# MiniBoard.net
KiCad netlist of a schematic drawn in EAGLE
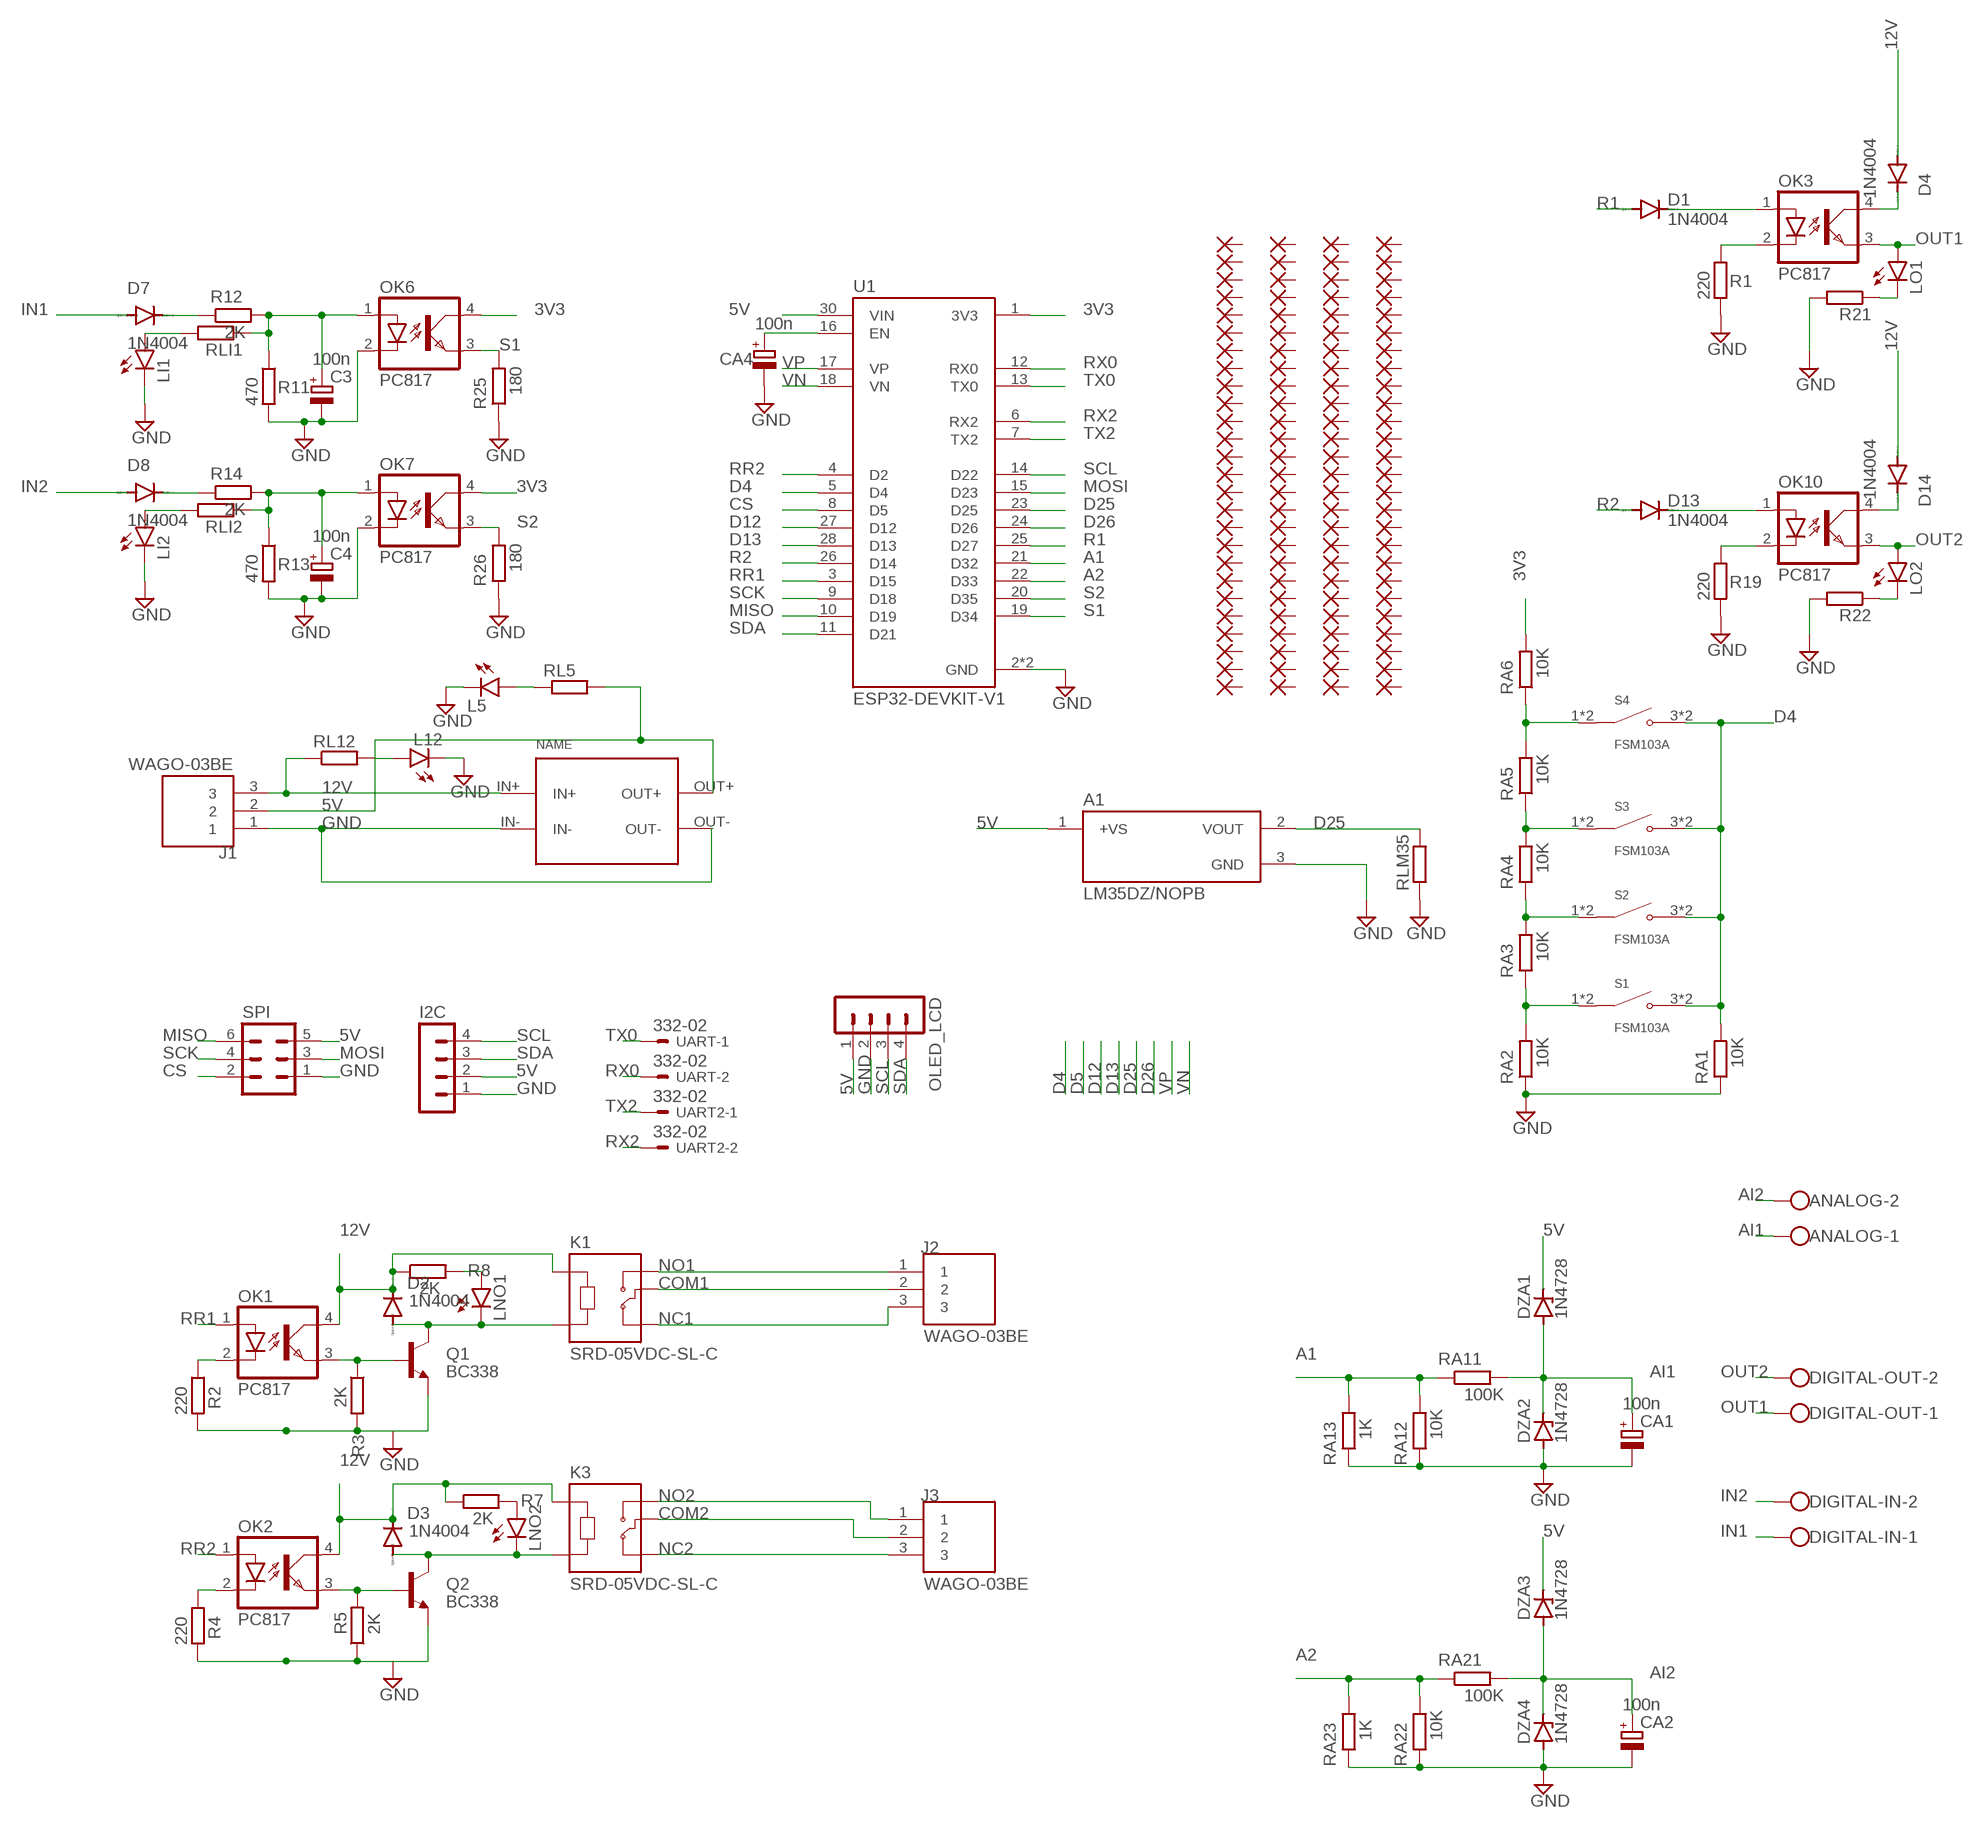
[diagram p0: schematic, sheet 1]

(export (version "E")
  (design (tool "Eeschema 10.0.6"))
  (components
    (comp (ref "A1")
      (value "LM35DZ/NOPB")
      (footprint "eagle-import:TO92127P521H735-3")
      (fields (field (name "DIGIKEY_PART_NUMBER") "LM35DZ/NOPB-ND") (field (name "MF") "Texas"))
      (libsource (lib "eagle-import") (part "LM35DZ/NOPB"))
    )
    (comp (ref "ANALOG")
      (value "W237-102")
      (footprint "eagle-import:W237-102")
      (fields (field (name "MPN") "237-102"))
      (libsource (lib "eagle-import") (part "W237-102"))
    )
    (comp (ref "C3")
      (value "100n")
      (footprint "eagle-import:E5-6")
      (libsource (lib "eagle-import") (part "CPOL-EUE5-6"))
    )
    (comp (ref "C4")
      (value "100n")
      (footprint "eagle-import:E5-6")
      (libsource (lib "eagle-import") (part "CPOL-EUE5-6"))
    )
    (comp (ref "CA1")
      (value "100n")
      (footprint "eagle-import:E5-6")
      (libsource (lib "eagle-import") (part "CPOL-EUE5-6"))
    )
    (comp (ref "CA2")
      (value "100n")
      (footprint "eagle-import:E5-6")
      (libsource (lib "eagle-import") (part "CPOL-EUE5-6"))
    )
    (comp (ref "CA4")
      (value "100n")
      (footprint "eagle-import:E5-6")
      (libsource (lib "eagle-import") (part "CPOL-EUE5-6"))
    )
    (comp (ref "D1")
      (value "1N4004")
      (footprint "eagle-import:DO41-10")
      (libsource (lib "eagle-import") (part "1N4004"))
    )
    (comp (ref "D2")
      (value "1N4004")
      (footprint "eagle-import:DO41-10")
      (libsource (lib "eagle-import") (part "1N4004"))
    )
    (comp (ref "D3")
      (value "1N4004")
      (footprint "eagle-import:DO41-10")
      (libsource (lib "eagle-import") (part "1N4004"))
    )
    (comp (ref "D4")
      (value "1N4004")
      (footprint "eagle-import:DO41-10")
      (libsource (lib "eagle-import") (part "1N4004"))
    )
    (comp (ref "D7")
      (value "1N4004")
      (footprint "eagle-import:DO41-10")
      (libsource (lib "eagle-import") (part "1N4004"))
    )
    (comp (ref "D8")
      (value "1N4004")
      (footprint "eagle-import:DO41-10")
      (libsource (lib "eagle-import") (part "1N4004"))
    )
    (comp (ref "D13")
      (value "1N4004")
      (footprint "eagle-import:DO41-10")
      (libsource (lib "eagle-import") (part "1N4004"))
    )
    (comp (ref "D14")
      (value "1N4004")
      (footprint "eagle-import:DO41-10")
      (libsource (lib "eagle-import") (part "1N4004"))
    )
    (comp (ref "DIGITAL-IN")
      (value "W237-102")
      (footprint "eagle-import:W237-102")
      (fields (field (name "MPN") "237-102"))
      (libsource (lib "eagle-import") (part "W237-102"))
    )
    (comp (ref "DIGITAL-OUT")
      (value "W237-102")
      (footprint "eagle-import:W237-102")
      (fields (field (name "MPN") "237-102"))
      (libsource (lib "eagle-import") (part "W237-102"))
    )
    (comp (ref "DZA1")
      (value "1N4728")
      (footprint "eagle-import:DO41Z10")
      (libsource (lib "eagle-import") (part "1N4728"))
    )
    (comp (ref "DZA2")
      (value "1N4728")
      (footprint "eagle-import:DO41Z10")
      (libsource (lib "eagle-import") (part "1N4728"))
    )
    (comp (ref "DZA3")
      (value "1N4728")
      (footprint "eagle-import:DO41Z10")
      (libsource (lib "eagle-import") (part "1N4728"))
    )
    (comp (ref "DZA4")
      (value "1N4728")
      (footprint "eagle-import:DO41Z10")
      (libsource (lib "eagle-import") (part "1N4728"))
    )
    (comp (ref "I2C")
      (value "MA04-1")
      (footprint "eagle-import:MA04-1")
      (libsource (lib "eagle-import") (part "MA04-1"))
    )
    (comp (ref "J1")
      (value "WAGO-03BE")
      (footprint "eagle-import:CUI_TB006-508-03BE")
      (fields (field (name "MF") "Same Sky") (field (name "MP") "TB006-508-03BE"))
      (libsource (lib "eagle-import") (part "WAGO-03BE"))
    )
    (comp (ref "J2")
      (value "WAGO-03BE")
      (footprint "eagle-import:CUI_TB006-508-03BE")
      (fields (field (name "MF") "Same Sky") (field (name "MP") "TB006-508-03BE"))
      (libsource (lib "eagle-import") (part "WAGO-03BE"))
    )
    (comp (ref "J3")
      (value "WAGO-03BE")
      (footprint "eagle-import:CUI_TB006-508-03BE")
      (fields (field (name "MF") "Same Sky") (field (name "MP") "TB006-508-03BE"))
      (libsource (lib "eagle-import") (part "WAGO-03BE"))
    )
    (comp (ref "K1")
      (value "SRD-05VDC-SL-C")
      (footprint "eagle-import:RELAY_SRD-05VDC-SL-C")
      (fields (field (name "MF") "Songle Relay"))
      (libsource (lib "eagle-import") (part "SRD-05VDC-SL-C"))
    )
    (comp (ref "K3")
      (value "SRD-05VDC-SL-C")
      (footprint "eagle-import:RELAY_SRD-05VDC-SL-C")
      (fields (field (name "MF") "Songle Relay"))
      (libsource (lib "eagle-import") (part "SRD-05VDC-SL-C"))
    )
    (comp (ref "L5")
      (value "LED3MM")
      (footprint "eagle-import:LED3MM")
      (libsource (lib "eagle-import") (part "LED3MM"))
    )
    (comp (ref "L12")
      (value "LED3MM")
      (footprint "eagle-import:LED3MM")
      (libsource (lib "eagle-import") (part "LED3MM"))
    )
    (comp (ref "LI1")
      (value "LED3MM")
      (footprint "eagle-import:LED3MM")
      (libsource (lib "eagle-import") (part "LED3MM"))
    )
    (comp (ref "LI2")
      (value "LED3MM")
      (footprint "eagle-import:LED3MM")
      (libsource (lib "eagle-import") (part "LED3MM"))
    )
    (comp (ref "LNO1")
      (value "LED3MM")
      (footprint "eagle-import:LED3MM")
      (libsource (lib "eagle-import") (part "LED3MM"))
    )
    (comp (ref "LNO2")
      (value "LED3MM")
      (footprint "eagle-import:LED3MM")
      (libsource (lib "eagle-import") (part "LED3MM"))
    )
    (comp (ref "LO1")
      (value "LED3MM")
      (footprint "eagle-import:LED3MM")
      (libsource (lib "eagle-import") (part "LED3MM"))
    )
    (comp (ref "LO2")
      (value "LED3MM")
      (footprint "eagle-import:LED3MM")
      (libsource (lib "eagle-import") (part "LED3MM"))
    )
    (comp (ref "OK1")
      (value "PC817")
      (footprint "eagle-import:DIL04")
      (fields (field (name "MPN") "PC817X4J000F"))
      (libsource (lib "eagle-import") (part "PC817"))
    )
    (comp (ref "OK2")
      (value "PC817")
      (footprint "eagle-import:DIL04")
      (fields (field (name "MPN") "PC817X4J000F"))
      (libsource (lib "eagle-import") (part "PC817"))
    )
    (comp (ref "OK3")
      (value "PC817")
      (footprint "eagle-import:DIL04")
      (fields (field (name "MPN") "PC817X4J000F"))
      (libsource (lib "eagle-import") (part "PC817"))
    )
    (comp (ref "OK6")
      (value "PC817")
      (footprint "eagle-import:DIL04")
      (fields (field (name "MPN") "PC817X4J000F"))
      (libsource (lib "eagle-import") (part "PC817"))
    )
    (comp (ref "OK7")
      (value "PC817")
      (footprint "eagle-import:DIL04")
      (fields (field (name "MPN") "PC817X4J000F"))
      (libsource (lib "eagle-import") (part "PC817"))
    )
    (comp (ref "OK10")
      (value "PC817")
      (footprint "eagle-import:DIL04")
      (fields (field (name "MPN") "PC817X4J000F"))
      (libsource (lib "eagle-import") (part "PC817"))
    )
    (comp (ref "OLED_LCD")
      (value "MA04-1")
      (footprint "eagle-import:MA04-1")
      (libsource (lib "eagle-import") (part "MA04-1"))
    )
    (comp (ref "PAD1")
      (value "WIREPAD1,6/0,9")
      (footprint "eagle-import:1,6_0,9")
      (libsource (lib "eagle-import") (part "WIREPAD1,6/0,9"))
    )
    (comp (ref "PAD2")
      (value "WIREPAD1,6/0,9")
      (footprint "eagle-import:1,6_0,9")
      (libsource (lib "eagle-import") (part "WIREPAD1,6/0,9"))
    )
    (comp (ref "PAD3")
      (value "WIREPAD1,6/0,9")
      (footprint "eagle-import:1,6_0,9")
      (libsource (lib "eagle-import") (part "WIREPAD1,6/0,9"))
    )
    (comp (ref "PAD4")
      (value "WIREPAD1,6/0,9")
      (footprint "eagle-import:1,6_0,9")
      (libsource (lib "eagle-import") (part "WIREPAD1,6/0,9"))
    )
    (comp (ref "PAD5")
      (value "WIREPAD1,6/0,9")
      (footprint "eagle-import:1,6_0,9")
      (libsource (lib "eagle-import") (part "WIREPAD1,6/0,9"))
    )
    (comp (ref "PAD6")
      (value "WIREPAD1,6/0,9")
      (footprint "eagle-import:1,6_0,9")
      (libsource (lib "eagle-import") (part "WIREPAD1,6/0,9"))
    )
    (comp (ref "PAD7")
      (value "WIREPAD1,6/0,9")
      (footprint "eagle-import:1,6_0,9")
      (libsource (lib "eagle-import") (part "WIREPAD1,6/0,9"))
    )
    (comp (ref "PAD8")
      (value "WIREPAD1,6/0,9")
      (footprint "eagle-import:1,6_0,9")
      (libsource (lib "eagle-import") (part "WIREPAD1,6/0,9"))
    )
    (comp (ref "PAD9")
      (value "WIREPAD1,6/0,9")
      (footprint "eagle-import:1,6_0,9")
      (libsource (lib "eagle-import") (part "WIREPAD1,6/0,9"))
    )
    (comp (ref "PAD10")
      (value "WIREPAD1,6/0,9")
      (footprint "eagle-import:1,6_0,9")
      (libsource (lib "eagle-import") (part "WIREPAD1,6/0,9"))
    )
    (comp (ref "PAD11")
      (value "WIREPAD1,6/0,9")
      (footprint "eagle-import:1,6_0,9")
      (libsource (lib "eagle-import") (part "WIREPAD1,6/0,9"))
    )
    (comp (ref "PAD12")
      (value "WIREPAD1,6/0,9")
      (footprint "eagle-import:1,6_0,9")
      (libsource (lib "eagle-import") (part "WIREPAD1,6/0,9"))
    )
    (comp (ref "PAD13")
      (value "WIREPAD1,6/0,9")
      (footprint "eagle-import:1,6_0,9")
      (libsource (lib "eagle-import") (part "WIREPAD1,6/0,9"))
    )
    (comp (ref "PAD14")
      (value "WIREPAD1,6/0,9")
      (footprint "eagle-import:1,6_0,9")
      (libsource (lib "eagle-import") (part "WIREPAD1,6/0,9"))
    )
    (comp (ref "PAD15")
      (value "WIREPAD1,6/0,9")
      (footprint "eagle-import:1,6_0,9")
      (libsource (lib "eagle-import") (part "WIREPAD1,6/0,9"))
    )
    (comp (ref "PAD16")
      (value "WIREPAD1,6/0,9")
      (footprint "eagle-import:1,6_0,9")
      (libsource (lib "eagle-import") (part "WIREPAD1,6/0,9"))
    )
    (comp (ref "PAD17")
      (value "WIREPAD1,6/0,9")
      (footprint "eagle-import:1,6_0,9")
      (libsource (lib "eagle-import") (part "WIREPAD1,6/0,9"))
    )
    (comp (ref "PAD18")
      (value "WIREPAD1,6/0,9")
      (footprint "eagle-import:1,6_0,9")
      (libsource (lib "eagle-import") (part "WIREPAD1,6/0,9"))
    )
    (comp (ref "PAD19")
      (value "WIREPAD1,6/0,9")
      (footprint "eagle-import:1,6_0,9")
      (libsource (lib "eagle-import") (part "WIREPAD1,6/0,9"))
    )
    (comp (ref "PAD20")
      (value "WIREPAD1,6/0,9")
      (footprint "eagle-import:1,6_0,9")
      (libsource (lib "eagle-import") (part "WIREPAD1,6/0,9"))
    )
    (comp (ref "PAD21")
      (value "WIREPAD1,6/0,9")
      (footprint "eagle-import:1,6_0,9")
      (libsource (lib "eagle-import") (part "WIREPAD1,6/0,9"))
    )
    (comp (ref "PAD22")
      (value "WIREPAD1,6/0,9")
      (footprint "eagle-import:1,6_0,9")
      (libsource (lib "eagle-import") (part "WIREPAD1,6/0,9"))
    )
    (comp (ref "PAD23")
      (value "WIREPAD1,6/0,9")
      (footprint "eagle-import:1,6_0,9")
      (libsource (lib "eagle-import") (part "WIREPAD1,6/0,9"))
    )
    (comp (ref "PAD24")
      (value "WIREPAD1,6/0,9")
      (footprint "eagle-import:1,6_0,9")
      (libsource (lib "eagle-import") (part "WIREPAD1,6/0,9"))
    )
    (comp (ref "PAD25")
      (value "WIREPAD1,6/0,9")
      (footprint "eagle-import:1,6_0,9")
      (libsource (lib "eagle-import") (part "WIREPAD1,6/0,9"))
    )
    (comp (ref "PAD26")
      (value "WIREPAD1,6/0,9")
      (footprint "eagle-import:1,6_0,9")
      (libsource (lib "eagle-import") (part "WIREPAD1,6/0,9"))
    )
    (comp (ref "PAD27")
      (value "WIREPAD1,6/0,9")
      (footprint "eagle-import:1,6_0,9")
      (libsource (lib "eagle-import") (part "WIREPAD1,6/0,9"))
    )
    (comp (ref "PAD28")
      (value "WIREPAD1,6/0,9")
      (footprint "eagle-import:1,6_0,9")
      (libsource (lib "eagle-import") (part "WIREPAD1,6/0,9"))
    )
    (comp (ref "PAD29")
      (value "WIREPAD1,6/0,9")
      (footprint "eagle-import:1,6_0,9")
      (libsource (lib "eagle-import") (part "WIREPAD1,6/0,9"))
    )
    (comp (ref "PAD30")
      (value "WIREPAD1,6/0,9")
      (footprint "eagle-import:1,6_0,9")
      (libsource (lib "eagle-import") (part "WIREPAD1,6/0,9"))
    )
    (comp (ref "PAD31")
      (value "WIREPAD1,6/0,9")
      (footprint "eagle-import:1,6_0,9")
      (libsource (lib "eagle-import") (part "WIREPAD1,6/0,9"))
    )
    (comp (ref "PAD32")
      (value "WIREPAD1,6/0,9")
      (footprint "eagle-import:1,6_0,9")
      (libsource (lib "eagle-import") (part "WIREPAD1,6/0,9"))
    )
    (comp (ref "PAD33")
      (value "WIREPAD1,6/0,9")
      (footprint "eagle-import:1,6_0,9")
      (libsource (lib "eagle-import") (part "WIREPAD1,6/0,9"))
    )
    (comp (ref "PAD34")
      (value "WIREPAD1,6/0,9")
      (footprint "eagle-import:1,6_0,9")
      (libsource (lib "eagle-import") (part "WIREPAD1,6/0,9"))
    )
    (comp (ref "PAD35")
      (value "WIREPAD1,6/0,9")
      (footprint "eagle-import:1,6_0,9")
      (libsource (lib "eagle-import") (part "WIREPAD1,6/0,9"))
    )
    (comp (ref "PAD36")
      (value "WIREPAD1,6/0,9")
      (footprint "eagle-import:1,6_0,9")
      (libsource (lib "eagle-import") (part "WIREPAD1,6/0,9"))
    )
    (comp (ref "PAD37")
      (value "WIREPAD1,6/0,9")
      (footprint "eagle-import:1,6_0,9")
      (libsource (lib "eagle-import") (part "WIREPAD1,6/0,9"))
    )
    (comp (ref "PAD38")
      (value "WIREPAD1,6/0,9")
      (footprint "eagle-import:1,6_0,9")
      (libsource (lib "eagle-import") (part "WIREPAD1,6/0,9"))
    )
    (comp (ref "PAD39")
      (value "WIREPAD1,6/0,9")
      (footprint "eagle-import:1,6_0,9")
      (libsource (lib "eagle-import") (part "WIREPAD1,6/0,9"))
    )
    (comp (ref "PAD40")
      (value "WIREPAD1,6/0,9")
      (footprint "eagle-import:1,6_0,9")
      (libsource (lib "eagle-import") (part "WIREPAD1,6/0,9"))
    )
    (comp (ref "PAD41")
      (value "WIREPAD1,6/0,9")
      (footprint "eagle-import:1,6_0,9")
      (libsource (lib "eagle-import") (part "WIREPAD1,6/0,9"))
    )
    (comp (ref "PAD42")
      (value "WIREPAD1,6/0,9")
      (footprint "eagle-import:1,6_0,9")
      (libsource (lib "eagle-import") (part "WIREPAD1,6/0,9"))
    )
    (comp (ref "PAD43")
      (value "WIREPAD1,6/0,9")
      (footprint "eagle-import:1,6_0,9")
      (libsource (lib "eagle-import") (part "WIREPAD1,6/0,9"))
    )
    (comp (ref "PAD44")
      (value "WIREPAD1,6/0,9")
      (footprint "eagle-import:1,6_0,9")
      (libsource (lib "eagle-import") (part "WIREPAD1,6/0,9"))
    )
    (comp (ref "PAD45")
      (value "WIREPAD1,6/0,9")
      (footprint "eagle-import:1,6_0,9")
      (libsource (lib "eagle-import") (part "WIREPAD1,6/0,9"))
    )
    (comp (ref "PAD46")
      (value "WIREPAD1,6/0,9")
      (footprint "eagle-import:1,6_0,9")
      (libsource (lib "eagle-import") (part "WIREPAD1,6/0,9"))
    )
    (comp (ref "PAD47")
      (value "WIREPAD1,6/0,9")
      (footprint "eagle-import:1,6_0,9")
      (libsource (lib "eagle-import") (part "WIREPAD1,6/0,9"))
    )
    (comp (ref "PAD48")
      (value "WIREPAD1,6/0,9")
      (footprint "eagle-import:1,6_0,9")
      (libsource (lib "eagle-import") (part "WIREPAD1,6/0,9"))
    )
    (comp (ref "PAD49")
      (value "WIREPAD1,6/0,9")
      (footprint "eagle-import:1,6_0,9")
      (libsource (lib "eagle-import") (part "WIREPAD1,6/0,9"))
    )
    (comp (ref "PAD50")
      (value "WIREPAD1,6/0,9")
      (footprint "eagle-import:1,6_0,9")
      (libsource (lib "eagle-import") (part "WIREPAD1,6/0,9"))
    )
    (comp (ref "PAD51")
      (value "WIREPAD1,6/0,9")
      (footprint "eagle-import:1,6_0,9")
      (libsource (lib "eagle-import") (part "WIREPAD1,6/0,9"))
    )
    (comp (ref "PAD52")
      (value "WIREPAD1,6/0,9")
      (footprint "eagle-import:1,6_0,9")
      (libsource (lib "eagle-import") (part "WIREPAD1,6/0,9"))
    )
    (comp (ref "PAD53")
      (value "WIREPAD1,6/0,9")
      (footprint "eagle-import:1,6_0,9")
      (libsource (lib "eagle-import") (part "WIREPAD1,6/0,9"))
    )
    (comp (ref "PAD54")
      (value "WIREPAD1,6/0,9")
      (footprint "eagle-import:1,6_0,9")
      (libsource (lib "eagle-import") (part "WIREPAD1,6/0,9"))
    )
    (comp (ref "PAD55")
      (value "WIREPAD1,6/0,9")
      (footprint "eagle-import:1,6_0,9")
      (libsource (lib "eagle-import") (part "WIREPAD1,6/0,9"))
    )
    (comp (ref "PAD56")
      (value "WIREPAD1,6/0,9")
      (footprint "eagle-import:1,6_0,9")
      (libsource (lib "eagle-import") (part "WIREPAD1,6/0,9"))
    )
    (comp (ref "PAD57")
      (value "WIREPAD1,6/0,9")
      (footprint "eagle-import:1,6_0,9")
      (libsource (lib "eagle-import") (part "WIREPAD1,6/0,9"))
    )
    (comp (ref "PAD58")
      (value "WIREPAD1,6/0,9")
      (footprint "eagle-import:1,6_0,9")
      (libsource (lib "eagle-import") (part "WIREPAD1,6/0,9"))
    )
    (comp (ref "PAD59")
      (value "WIREPAD1,6/0,9")
      (footprint "eagle-import:1,6_0,9")
      (libsource (lib "eagle-import") (part "WIREPAD1,6/0,9"))
    )
    (comp (ref "PAD60")
      (value "WIREPAD1,6/0,9")
      (footprint "eagle-import:1,6_0,9")
      (libsource (lib "eagle-import") (part "WIREPAD1,6/0,9"))
    )
    (comp (ref "PAD61")
      (value "WIREPAD1,6/0,9")
      (footprint "eagle-import:1,6_0,9")
      (libsource (lib "eagle-import") (part "WIREPAD1,6/0,9"))
    )
    (comp (ref "PAD62")
      (value "WIREPAD1,6/0,9")
      (footprint "eagle-import:1,6_0,9")
      (libsource (lib "eagle-import") (part "WIREPAD1,6/0,9"))
    )
    (comp (ref "PAD63")
      (value "WIREPAD1,6/0,9")
      (footprint "eagle-import:1,6_0,9")
      (libsource (lib "eagle-import") (part "WIREPAD1,6/0,9"))
    )
    (comp (ref "PAD64")
      (value "WIREPAD1,6/0,9")
      (footprint "eagle-import:1,6_0,9")
      (libsource (lib "eagle-import") (part "WIREPAD1,6/0,9"))
    )
    (comp (ref "PAD65")
      (value "WIREPAD1,6/0,9")
      (footprint "eagle-import:1,6_0,9")
      (libsource (lib "eagle-import") (part "WIREPAD1,6/0,9"))
    )
    (comp (ref "PAD66")
      (value "WIREPAD1,6/0,9")
      (footprint "eagle-import:1,6_0,9")
      (libsource (lib "eagle-import") (part "WIREPAD1,6/0,9"))
    )
    (comp (ref "PAD67")
      (value "WIREPAD1,6/0,9")
      (footprint "eagle-import:1,6_0,9")
      (libsource (lib "eagle-import") (part "WIREPAD1,6/0,9"))
    )
    (comp (ref "PAD68")
      (value "WIREPAD1,6/0,9")
      (footprint "eagle-import:1,6_0,9")
      (libsource (lib "eagle-import") (part "WIREPAD1,6/0,9"))
    )
    (comp (ref "PAD69")
      (value "WIREPAD1,6/0,9")
      (footprint "eagle-import:1,6_0,9")
      (libsource (lib "eagle-import") (part "WIREPAD1,6/0,9"))
    )
    (comp (ref "PAD70")
      (value "WIREPAD1,6/0,9")
      (footprint "eagle-import:1,6_0,9")
      (libsource (lib "eagle-import") (part "WIREPAD1,6/0,9"))
    )
    (comp (ref "PAD71")
      (value "WIREPAD1,6/0,9")
      (footprint "eagle-import:1,6_0,9")
      (libsource (lib "eagle-import") (part "WIREPAD1,6/0,9"))
    )
    (comp (ref "PAD72")
      (value "WIREPAD1,6/0,9")
      (footprint "eagle-import:1,6_0,9")
      (libsource (lib "eagle-import") (part "WIREPAD1,6/0,9"))
    )
    (comp (ref "PAD73")
      (value "WIREPAD1,6/0,9")
      (footprint "eagle-import:1,6_0,9")
      (libsource (lib "eagle-import") (part "WIREPAD1,6/0,9"))
    )
    (comp (ref "PAD74")
      (value "WIREPAD1,6/0,9")
      (footprint "eagle-import:1,6_0,9")
      (libsource (lib "eagle-import") (part "WIREPAD1,6/0,9"))
    )
    (comp (ref "PAD75")
      (value "WIREPAD1,6/0,9")
      (footprint "eagle-import:1,6_0,9")
      (libsource (lib "eagle-import") (part "WIREPAD1,6/0,9"))
    )
    (comp (ref "PAD76")
      (value "WIREPAD1,6/0,9")
      (footprint "eagle-import:1,6_0,9")
      (libsource (lib "eagle-import") (part "WIREPAD1,6/0,9"))
    )
    (comp (ref "PAD77")
      (value "WIREPAD1,6/0,9")
      (footprint "eagle-import:1,6_0,9")
      (libsource (lib "eagle-import") (part "WIREPAD1,6/0,9"))
    )
    (comp (ref "PAD78")
      (value "WIREPAD1,6/0,9")
      (footprint "eagle-import:1,6_0,9")
      (libsource (lib "eagle-import") (part "WIREPAD1,6/0,9"))
    )
    (comp (ref "PAD79")
      (value "WIREPAD1,6/0,9")
      (footprint "eagle-import:1,6_0,9")
      (libsource (lib "eagle-import") (part "WIREPAD1,6/0,9"))
    )
    (comp (ref "PAD80")
      (value "WIREPAD1,6/0,9")
      (footprint "eagle-import:1,6_0,9")
      (libsource (lib "eagle-import") (part "WIREPAD1,6/0,9"))
    )
    (comp (ref "PAD81")
      (value "WIREPAD1,6/0,9")
      (footprint "eagle-import:1,6_0,9")
      (libsource (lib "eagle-import") (part "WIREPAD1,6/0,9"))
    )
    (comp (ref "PAD82")
      (value "WIREPAD1,6/0,9")
      (footprint "eagle-import:1,6_0,9")
      (libsource (lib "eagle-import") (part "WIREPAD1,6/0,9"))
    )
    (comp (ref "PAD83")
      (value "WIREPAD1,6/0,9")
      (footprint "eagle-import:1,6_0,9")
      (libsource (lib "eagle-import") (part "WIREPAD1,6/0,9"))
    )
    (comp (ref "PAD84")
      (value "WIREPAD1,6/0,9")
      (footprint "eagle-import:1,6_0,9")
      (libsource (lib "eagle-import") (part "WIREPAD1,6/0,9"))
    )
    (comp (ref "PAD85")
      (value "WIREPAD1,6/0,9")
      (footprint "eagle-import:1,6_0,9")
      (libsource (lib "eagle-import") (part "WIREPAD1,6/0,9"))
    )
    (comp (ref "PAD86")
      (value "WIREPAD1,6/0,9")
      (footprint "eagle-import:1,6_0,9")
      (libsource (lib "eagle-import") (part "WIREPAD1,6/0,9"))
    )
    (comp (ref "PAD87")
      (value "WIREPAD1,6/0,9")
      (footprint "eagle-import:1,6_0,9")
      (libsource (lib "eagle-import") (part "WIREPAD1,6/0,9"))
    )
    (comp (ref "PAD88")
      (value "WIREPAD1,6/0,9")
      (footprint "eagle-import:1,6_0,9")
      (libsource (lib "eagle-import") (part "WIREPAD1,6/0,9"))
    )
    (comp (ref "PAD89")
      (value "WIREPAD1,6/0,9")
      (footprint "eagle-import:1,6_0,9")
      (libsource (lib "eagle-import") (part "WIREPAD1,6/0,9"))
    )
    (comp (ref "PAD90")
      (value "WIREPAD1,6/0,9")
      (footprint "eagle-import:1,6_0,9")
      (libsource (lib "eagle-import") (part "WIREPAD1,6/0,9"))
    )
    (comp (ref "PAD91")
      (value "WIREPAD1,6/0,9")
      (footprint "eagle-import:1,6_0,9")
      (libsource (lib "eagle-import") (part "WIREPAD1,6/0,9"))
    )
    (comp (ref "PAD92")
      (value "WIREPAD1,6/0,9")
      (footprint "eagle-import:1,6_0,9")
      (libsource (lib "eagle-import") (part "WIREPAD1,6/0,9"))
    )
    (comp (ref "PAD93")
      (value "WIREPAD1,6/0,9")
      (footprint "eagle-import:1,6_0,9")
      (libsource (lib "eagle-import") (part "WIREPAD1,6/0,9"))
    )
    (comp (ref "PAD94")
      (value "WIREPAD1,6/0,9")
      (footprint "eagle-import:1,6_0,9")
      (libsource (lib "eagle-import") (part "WIREPAD1,6/0,9"))
    )
    (comp (ref "PAD95")
      (value "WIREPAD1,6/0,9")
      (footprint "eagle-import:1,6_0,9")
      (libsource (lib "eagle-import") (part "WIREPAD1,6/0,9"))
    )
    (comp (ref "PAD96")
      (value "WIREPAD1,6/0,9")
      (footprint "eagle-import:1,6_0,9")
      (libsource (lib "eagle-import") (part "WIREPAD1,6/0,9"))
    )
    (comp (ref "PAD97")
      (value "WIREPAD1,6/0,9")
      (footprint "eagle-import:1,6_0,9")
      (libsource (lib "eagle-import") (part "WIREPAD1,6/0,9"))
    )
    (comp (ref "PAD98")
      (value "WIREPAD1,6/0,9")
      (footprint "eagle-import:1,6_0,9")
      (libsource (lib "eagle-import") (part "WIREPAD1,6/0,9"))
    )
    (comp (ref "PAD99")
      (value "WIREPAD1,6/0,9")
      (footprint "eagle-import:1,6_0,9")
      (libsource (lib "eagle-import") (part "WIREPAD1,6/0,9"))
    )
    (comp (ref "PAD100")
      (value "WIREPAD1,6/0,9")
      (footprint "eagle-import:1,6_0,9")
      (libsource (lib "eagle-import") (part "WIREPAD1,6/0,9"))
    )
    (comp (ref "PAD101")
      (value "WIREPAD1,6/0,9")
      (footprint "eagle-import:1,6_0,9")
      (libsource (lib "eagle-import") (part "WIREPAD1,6/0,9"))
    )
    (comp (ref "PAD102")
      (value "WIREPAD1,6/0,9")
      (footprint "eagle-import:1,6_0,9")
      (libsource (lib "eagle-import") (part "WIREPAD1,6/0,9"))
    )
    (comp (ref "PAD103")
      (value "WIREPAD1,6/0,9")
      (footprint "eagle-import:1,6_0,9")
      (libsource (lib "eagle-import") (part "WIREPAD1,6/0,9"))
    )
    (comp (ref "PAD104")
      (value "WIREPAD1,6/0,9")
      (footprint "eagle-import:1,6_0,9")
      (libsource (lib "eagle-import") (part "WIREPAD1,6/0,9"))
    )
    (comp (ref "Q1")
      (value "BC338")
      (footprint "eagle-import:TO92-EBC")
      (libsource (lib "eagle-import") (part "BC338"))
    )
    (comp (ref "Q2")
      (value "BC338")
      (footprint "eagle-import:TO92-EBC")
      (libsource (lib "eagle-import") (part "BC338"))
    )
    (comp (ref "R1")
      (value "220")
      (footprint "eagle-import:0309_12")
      (libsource (lib "eagle-import") (part "R-EU_0309/12"))
    )
    (comp (ref "R2")
      (value "220")
      (footprint "eagle-import:0309_12")
      (libsource (lib "eagle-import") (part "R-EU_0309/12"))
    )
    (comp (ref "R3")
      (value "2K")
      (footprint "eagle-import:0309_12")
      (libsource (lib "eagle-import") (part "R-EU_0309/12"))
    )
    (comp (ref "R4")
      (value "220")
      (footprint "eagle-import:0309_12")
      (libsource (lib "eagle-import") (part "R-EU_0309/12"))
    )
    (comp (ref "R5")
      (value "2K")
      (footprint "eagle-import:0309_12")
      (libsource (lib "eagle-import") (part "R-EU_0309/12"))
    )
    (comp (ref "R7")
      (value "2K")
      (footprint "eagle-import:0309_12")
      (libsource (lib "eagle-import") (part "R-EU_0309/12"))
    )
    (comp (ref "R8")
      (value "2K")
      (footprint "eagle-import:0309_12")
      (libsource (lib "eagle-import") (part "R-EU_0309/12"))
    )
    (comp (ref "R11")
      (value "470")
      (footprint "eagle-import:0309_12")
      (libsource (lib "eagle-import") (part "R-EU_0309/12"))
    )
    (comp (ref "R12")
      (value "2K")
      (footprint "eagle-import:0309_12")
      (libsource (lib "eagle-import") (part "R-EU_0309/12"))
    )
    (comp (ref "R13")
      (value "470")
      (footprint "eagle-import:0309_12")
      (libsource (lib "eagle-import") (part "R-EU_0309/12"))
    )
    (comp (ref "R14")
      (value "2K")
      (footprint "eagle-import:0309_12")
      (libsource (lib "eagle-import") (part "R-EU_0309/12"))
    )
    (comp (ref "R19")
      (value "220")
      (footprint "eagle-import:0309_12")
      (libsource (lib "eagle-import") (part "R-EU_0309/12"))
    )
    (comp (ref "R21")
      (value "R-EU_0309/12")
      (footprint "eagle-import:0309_12")
      (libsource (lib "eagle-import") (part "R-EU_0309/12"))
    )
    (comp (ref "R22")
      (value "R-EU_0309/12")
      (footprint "eagle-import:0309_12")
      (libsource (lib "eagle-import") (part "R-EU_0309/12"))
    )
    (comp (ref "R25")
      (value "180")
      (footprint "eagle-import:0309_12")
      (libsource (lib "eagle-import") (part "R-EU_0309/12"))
    )
    (comp (ref "R26")
      (value "180")
      (footprint "eagle-import:0309_12")
      (libsource (lib "eagle-import") (part "R-EU_0309/12"))
    )
    (comp (ref "RA1")
      (value "10K")
      (footprint "eagle-import:0309_12")
      (libsource (lib "eagle-import") (part "R-EU_0309/12"))
    )
    (comp (ref "RA2")
      (value "10K")
      (footprint "eagle-import:0309_12")
      (libsource (lib "eagle-import") (part "R-EU_0309/12"))
    )
    (comp (ref "RA3")
      (value "10K")
      (footprint "eagle-import:0309_12")
      (libsource (lib "eagle-import") (part "R-EU_0309/12"))
    )
    (comp (ref "RA4")
      (value "10K")
      (footprint "eagle-import:0309_12")
      (libsource (lib "eagle-import") (part "R-EU_0309/12"))
    )
    (comp (ref "RA5")
      (value "10K")
      (footprint "eagle-import:0309_12")
      (libsource (lib "eagle-import") (part "R-EU_0309/12"))
    )
    (comp (ref "RA6")
      (value "10K")
      (footprint "eagle-import:0309_12")
      (libsource (lib "eagle-import") (part "R-EU_0309/12"))
    )
    (comp (ref "RA11")
      (value "100K")
      (footprint "eagle-import:0309_12")
      (libsource (lib "eagle-import") (part "R-EU_0309/12"))
    )
    (comp (ref "RA12")
      (value "10K")
      (footprint "eagle-import:0309_12")
      (libsource (lib "eagle-import") (part "R-EU_0309/12"))
    )
    (comp (ref "RA13")
      (value "1K")
      (footprint "eagle-import:0309_12")
      (libsource (lib "eagle-import") (part "R-EU_0309/12"))
    )
    (comp (ref "RA21")
      (value "100K")
      (footprint "eagle-import:0309_12")
      (libsource (lib "eagle-import") (part "R-EU_0309/12"))
    )
    (comp (ref "RA22")
      (value "10K")
      (footprint "eagle-import:0309_12")
      (libsource (lib "eagle-import") (part "R-EU_0309/12"))
    )
    (comp (ref "RA23")
      (value "1K")
      (footprint "eagle-import:0309_12")
      (libsource (lib "eagle-import") (part "R-EU_0309/12"))
    )
    (comp (ref "RL5")
      (value "R-EU_0309/12")
      (footprint "eagle-import:0309_12")
      (libsource (lib "eagle-import") (part "R-EU_0309/12"))
    )
    (comp (ref "RL12")
      (value "R-EU_0309/12")
      (footprint "eagle-import:0309_12")
      (libsource (lib "eagle-import") (part "R-EU_0309/12"))
    )
    (comp (ref "RLI1")
      (value "R-EU_0309/12")
      (footprint "eagle-import:0309_12")
      (libsource (lib "eagle-import") (part "R-EU_0309/12"))
    )
    (comp (ref "RLI2")
      (value "R-EU_0309/12")
      (footprint "eagle-import:0309_12")
      (libsource (lib "eagle-import") (part "R-EU_0309/12"))
    )
    (comp (ref "RLM35")
      (value "R-EU_0309/12")
      (footprint "eagle-import:0309_12")
      (libsource (lib "eagle-import") (part "R-EU_0309/12"))
    )
    (comp (ref "S1")
      (value "FSM103A")
      (footprint "eagle-import:SW_1571627-1")
      (fields (field (name "COMMENT") "1571627-1") (field (name "MF") "TE Connectivity"))
      (libsource (lib "eagle-import") (part "FSM103A"))
    )
    (comp (ref "S2")
      (value "FSM103A")
      (footprint "eagle-import:SW_1571627-1")
      (fields (field (name "COMMENT") "1571627-1") (field (name "MF") "TE Connectivity"))
      (libsource (lib "eagle-import") (part "FSM103A"))
    )
    (comp (ref "S3")
      (value "FSM103A")
      (footprint "eagle-import:SW_1571627-1")
      (fields (field (name "COMMENT") "1571627-1") (field (name "MF") "TE Connectivity"))
      (libsource (lib "eagle-import") (part "FSM103A"))
    )
    (comp (ref "S4")
      (value "FSM103A")
      (footprint "eagle-import:SW_1571627-1")
      (fields (field (name "COMMENT") "1571627-1") (field (name "MF") "TE Connectivity"))
      (libsource (lib "eagle-import") (part "FSM103A"))
    )
    (comp (ref "SPI")
      (value "MA03-2")
      (footprint "eagle-import:MA03-2")
      (libsource (lib "eagle-import") (part "MA03-2"))
    )
    (comp (ref "U$1")
      (value "CP8-ADJ")
      (footprint "eagle-import:CP8-ADJ")
      (libsource (lib "eagle-import") (part "CP8-ADJ"))
    )
    (comp (ref "U1")
      (value "ESP32-DEVKIT-V1")
      (footprint "eagle-import:MODULE_ESP32_DEVKIT_V1")
      (fields (field (name "MF") "Do it"))
      (libsource (lib "eagle-import") (part "ESP32-DEVKIT-V1"))
    )
    (comp (ref "UART")
      (value "332-02")
      (footprint "eagle-import:332-02")
      (libsource (lib "eagle-import") (part "332-02"))
    )
    (comp (ref "UART2")
      (value "332-02")
      (footprint "eagle-import:332-02")
      (libsource (lib "eagle-import") (part "332-02"))
    )
  )
  (nets
    (net (code "1") (name "/3V3") (class "Default")
      (node (ref "OK6") (pin "4") (pinfunction "COL_4") (pintype "passive"))
      (node (ref "OK7") (pin "4") (pinfunction "COL_4") (pintype "passive"))
      (node (ref "RA6") (pin "2") (pinfunction "2_2") (pintype "passive"))
      (node (ref "U1") (pin "1") (pinfunction "3V3_1") (pintype "output"))
    )
    (net (code "2") (name "/5V") (class "Default")
      (node (ref "A1") (pin "1") (pinfunction "+VS_1") (pintype "power_in"))
      (node (ref "DZA1") (pin "C") (pinfunction "C_C") (pintype "passive"))
      (node (ref "DZA3") (pin "C") (pinfunction "C_C") (pintype "passive"))
      (node (ref "I2C") (pin "2") (pinfunction "2_2") (pintype "passive"))
      (node (ref "J1") (pin "2") (pinfunction "2_2") (pintype "passive"))
      (node (ref "OLED_LCD") (pin "1") (pinfunction "1_1") (pintype "passive"))
      (node (ref "RL5") (pin "2") (pinfunction "2_2") (pintype "passive"))
      (node (ref "SPI") (pin "5") (pinfunction "5_5") (pintype "passive"))
      (node (ref "U$1") (pin "OUT+") (pinfunction "OUT+_OUT+") (pintype "passive"))
      (node (ref "U1") (pin "30") (pinfunction "VIN_30") (pintype "input"))
    )
    (net (code "3") (name "/12V") (class "Default")
      (node (ref "D14") (pin "A") (pinfunction "A_A") (pintype "passive"))
      (node (ref "D2") (pin "C") (pinfunction "C_C") (pintype "passive"))
      (node (ref "D3") (pin "C") (pinfunction "C_C") (pintype "passive"))
      (node (ref "D4") (pin "A") (pinfunction "A_A") (pintype "passive"))
      (node (ref "J1") (pin "3") (pinfunction "3_3") (pintype "passive"))
      (node (ref "K1") (pin "A1") (pinfunction "A1_A1") (pintype "passive"))
      (node (ref "K3") (pin "A1") (pinfunction "A1_A1") (pintype "passive"))
      (node (ref "OK1") (pin "4") (pinfunction "COL_4") (pintype "passive"))
      (node (ref "OK2") (pin "4") (pinfunction "COL_4") (pintype "passive"))
      (node (ref "R7") (pin "1") (pinfunction "1_1") (pintype "passive"))
      (node (ref "R8") (pin "1") (pinfunction "1_1") (pintype "passive"))
      (node (ref "RL12") (pin "1") (pinfunction "1_1") (pintype "passive"))
      (node (ref "U$1") (pin "IN+") (pinfunction "IN+_IN+") (pintype "passive"))
    )
    (net (code "4") (name "/A1") (class "Default")
      (node (ref "RA11") (pin "1") (pinfunction "1_1") (pintype "passive"))
      (node (ref "RA12") (pin "2") (pinfunction "2_2") (pintype "passive"))
      (node (ref "RA13") (pin "2") (pinfunction "2_2") (pintype "passive"))
      (node (ref "U1") (pin "21") (pinfunction "D32_21") (pintype "bidirectional"))
    )
    (net (code "5") (name "/A2") (class "Default")
      (node (ref "RA21") (pin "1") (pinfunction "1_1") (pintype "passive"))
      (node (ref "RA22") (pin "2") (pinfunction "2_2") (pintype "passive"))
      (node (ref "RA23") (pin "2") (pinfunction "2_2") (pintype "passive"))
      (node (ref "U1") (pin "22") (pinfunction "D33_22") (pintype "bidirectional"))
    )
    (net (code "6") (name "/AI1") (class "Default")
      (node (ref "ANALOG") (pin "1") (pinfunction "KL_1") (pintype "passive"))
      (node (ref "CA1") (pin "+") (pinfunction "+_+") (pintype "passive"))
      (node (ref "DZA1") (pin "A") (pinfunction "A_A") (pintype "passive"))
      (node (ref "DZA2") (pin "C") (pinfunction "C_C") (pintype "passive"))
      (node (ref "RA11") (pin "2") (pinfunction "2_2") (pintype "passive"))
    )
    (net (code "7") (name "/AI2") (class "Default")
      (node (ref "ANALOG") (pin "2") (pinfunction "KL_2") (pintype "passive"))
      (node (ref "CA2") (pin "+") (pinfunction "+_+") (pintype "passive"))
      (node (ref "DZA3") (pin "A") (pinfunction "A_A") (pintype "passive"))
      (node (ref "DZA4") (pin "C") (pinfunction "C_C") (pintype "passive"))
      (node (ref "RA21") (pin "2") (pinfunction "2_2") (pintype "passive"))
    )
    (net (code "8") (name "/COM1") (class "Default")
      (node (ref "J2") (pin "2") (pinfunction "2_2") (pintype "passive"))
      (node (ref "K1") (pin "COM") (pinfunction "COM_COM") (pintype "passive"))
    )
    (net (code "9") (name "/COM2") (class "Default")
      (node (ref "J3") (pin "2") (pinfunction "2_2") (pintype "passive"))
      (node (ref "K3") (pin "COM") (pinfunction "COM_COM") (pintype "passive"))
    )
    (net (code "10") (name "/CS") (class "Default")
      (node (ref "SPI") (pin "2") (pinfunction "2_2") (pintype "passive"))
      (node (ref "U1") (pin "8") (pinfunction "D5_8") (pintype "bidirectional"))
    )
    (net (code "11") (name "/D4") (class "Default")
      (node (ref "RA1") (pin "2") (pinfunction "2_2") (pintype "passive"))
      (node (ref "S1") (pin "3") (pinfunction "NO_3") (pintype "passive"))
      (node (ref "S1") (pin "4") (pinfunction "NO_4") (pintype "passive"))
      (node (ref "S2") (pin "3") (pinfunction "NO_3") (pintype "passive"))
      (node (ref "S2") (pin "4") (pinfunction "NO_4") (pintype "passive"))
      (node (ref "S3") (pin "3") (pinfunction "NO_3") (pintype "passive"))
      (node (ref "S3") (pin "4") (pinfunction "NO_4") (pintype "passive"))
      (node (ref "S4") (pin "3") (pinfunction "NO_3") (pintype "passive"))
      (node (ref "S4") (pin "4") (pinfunction "NO_4") (pintype "passive"))
      (node (ref "U1") (pin "5") (pinfunction "D4_5") (pintype "bidirectional"))
    )
    (net (code "13") (name "/D12") (class "Default")
      (node (ref "U1") (pin "27") (pinfunction "D12_27") (pintype "bidirectional"))
    )
    (net (code "14") (name "/D13") (class "Default")
      (node (ref "U1") (pin "28") (pinfunction "D13_28") (pintype "bidirectional"))
    )
    (net (code "15") (name "/D25") (class "Default")
      (node (ref "A1") (pin "2") (pinfunction "VOUT_2") (pintype "output"))
      (node (ref "RLM35") (pin "2") (pinfunction "2_2") (pintype "passive"))
      (node (ref "U1") (pin "23") (pinfunction "D25_23") (pintype "bidirectional"))
    )
    (net (code "16") (name "/D26") (class "Default")
      (node (ref "U1") (pin "24") (pinfunction "D26_24") (pintype "bidirectional"))
    )
    (net (code "17") (name "/IN1") (class "Default")
      (node (ref "D7") (pin "A") (pinfunction "A_A") (pintype "passive"))
      (node (ref "DIGITAL-IN") (pin "1") (pinfunction "KL_1") (pintype "passive"))
    )
    (net (code "18") (name "/IN2") (class "Default")
      (node (ref "D8") (pin "A") (pinfunction "A_A") (pintype "passive"))
      (node (ref "DIGITAL-IN") (pin "2") (pinfunction "KL_2") (pintype "passive"))
    )
    (net (code "19") (name "/MISO") (class "Default")
      (node (ref "SPI") (pin "6") (pinfunction "6_6") (pintype "passive"))
      (node (ref "U1") (pin "10") (pinfunction "D19_10") (pintype "bidirectional"))
    )
    (net (code "20") (name "/MOSI") (class "Default")
      (node (ref "SPI") (pin "3") (pinfunction "3_3") (pintype "passive"))
      (node (ref "U1") (pin "15") (pinfunction "D23_15") (pintype "bidirectional"))
    )
    (net (code "21") (name "/NC1") (class "Default")
      (node (ref "J2") (pin "3") (pinfunction "3_3") (pintype "passive"))
      (node (ref "K1") (pin "NC") (pinfunction "NC_NC") (pintype "passive"))
    )
    (net (code "22") (name "/NC2") (class "Default")
      (node (ref "J3") (pin "3") (pinfunction "3_3") (pintype "passive"))
      (node (ref "K3") (pin "NC") (pinfunction "NC_NC") (pintype "passive"))
    )
    (net (code "23") (name "/NO1") (class "Default")
      (node (ref "J2") (pin "1") (pinfunction "1_1") (pintype "passive"))
      (node (ref "K1") (pin "NO") (pinfunction "NO_NO") (pintype "passive"))
    )
    (net (code "24") (name "/NO2") (class "Default")
      (node (ref "J3") (pin "1") (pinfunction "1_1") (pintype "passive"))
      (node (ref "K3") (pin "NO") (pinfunction "NO_NO") (pintype "passive"))
    )
    (net (code "25") (name "/OUT1") (class "Default")
      (node (ref "DIGITAL-OUT") (pin "1") (pinfunction "KL_1") (pintype "passive"))
      (node (ref "LO1") (pin "A") (pinfunction "A_A") (pintype "passive"))
      (node (ref "OK3") (pin "3") (pinfunction "EMIT_3") (pintype "passive"))
    )
    (net (code "26") (name "/OUT2") (class "Default")
      (node (ref "DIGITAL-OUT") (pin "2") (pinfunction "KL_2") (pintype "passive"))
      (node (ref "LO2") (pin "A") (pinfunction "A_A") (pintype "passive"))
      (node (ref "OK10") (pin "3") (pinfunction "EMIT_3") (pintype "passive"))
    )
    (net (code "27") (name "/R1") (class "Default")
      (node (ref "D1") (pin "A") (pinfunction "A_A") (pintype "passive"))
      (node (ref "U1") (pin "25") (pinfunction "D27_25") (pintype "bidirectional"))
    )
    (net (code "28") (name "/R2") (class "Default")
      (node (ref "D13") (pin "A") (pinfunction "A_A") (pintype "passive"))
      (node (ref "U1") (pin "26") (pinfunction "D14_26") (pintype "bidirectional"))
    )
    (net (code "29") (name "/RR1") (class "Default")
      (node (ref "OK1") (pin "1") (pinfunction "A_1") (pintype "passive"))
      (node (ref "U1") (pin "3") (pinfunction "D15_3") (pintype "bidirectional"))
    )
    (net (code "30") (name "/RR2") (class "Default")
      (node (ref "OK2") (pin "1") (pinfunction "A_1") (pintype "passive"))
      (node (ref "U1") (pin "4") (pinfunction "D2_4") (pintype "bidirectional"))
    )
    (net (code "31") (name "/RX0") (class "Default")
      (node (ref "U1") (pin "12") (pinfunction "RX0_12") (pintype "input"))
      (node (ref "UART") (pin "2") (pinfunction "S_2") (pintype "passive"))
    )
    (net (code "32") (name "/RX2") (class "Default")
      (node (ref "U1") (pin "6") (pinfunction "RX2_6") (pintype "input"))
      (node (ref "UART2") (pin "2") (pinfunction "S_2") (pintype "passive"))
    )
    (net (code "33") (name "/S1") (class "Default")
      (node (ref "OK6") (pin "3") (pinfunction "EMIT_3") (pintype "passive"))
      (node (ref "R25") (pin "2") (pinfunction "2_2") (pintype "passive"))
      (node (ref "U1") (pin "19") (pinfunction "D34_19") (pintype "bidirectional"))
    )
    (net (code "34") (name "/S2") (class "Default")
      (node (ref "OK7") (pin "3") (pinfunction "EMIT_3") (pintype "passive"))
      (node (ref "R26") (pin "2") (pinfunction "2_2") (pintype "passive"))
      (node (ref "U1") (pin "20") (pinfunction "D35_20") (pintype "bidirectional"))
    )
    (net (code "35") (name "/SCK") (class "Default")
      (node (ref "SPI") (pin "4") (pinfunction "4_4") (pintype "passive"))
      (node (ref "U1") (pin "9") (pinfunction "D18_9") (pintype "bidirectional"))
    )
    (net (code "36") (name "/SCL") (class "Default")
      (node (ref "I2C") (pin "4") (pinfunction "4_4") (pintype "passive"))
      (node (ref "OLED_LCD") (pin "3") (pinfunction "3_3") (pintype "passive"))
      (node (ref "U1") (pin "14") (pinfunction "D22_14") (pintype "bidirectional"))
    )
    (net (code "37") (name "/SDA") (class "Default")
      (node (ref "I2C") (pin "3") (pinfunction "3_3") (pintype "passive"))
      (node (ref "OLED_LCD") (pin "4") (pinfunction "4_4") (pintype "passive"))
      (node (ref "U1") (pin "11") (pinfunction "D21_11") (pintype "bidirectional"))
    )
    (net (code "38") (name "/TX0") (class "Default")
      (node (ref "U1") (pin "13") (pinfunction "TX0_13") (pintype "output"))
      (node (ref "UART") (pin "1") (pinfunction "S_1") (pintype "passive"))
    )
    (net (code "39") (name "/TX2") (class "Default")
      (node (ref "U1") (pin "7") (pinfunction "TX2_7") (pintype "output"))
      (node (ref "UART2") (pin "1") (pinfunction "S_1") (pintype "passive"))
    )
    (net (code "40") (name "/VN") (class "Default")
      (node (ref "U1") (pin "18") (pinfunction "VN_18") (pintype "bidirectional"))
    )
    (net (code "41") (name "/VP") (class "Default")
      (node (ref "U1") (pin "17") (pinfunction "VP_17") (pintype "bidirectional"))
    )
    (net (code "42") (name "GND") (class "Default")
      (node (ref "A1") (pin "3") (pinfunction "GND_3") (pintype "power_in"))
      (node (ref "C3") (pin "-") (pinfunction "-_-") (pintype "passive"))
      (node (ref "C4") (pin "-") (pinfunction "-_-") (pintype "passive"))
      (node (ref "CA1") (pin "-") (pinfunction "-_-") (pintype "passive"))
      (node (ref "CA2") (pin "-") (pinfunction "-_-") (pintype "passive"))
      (node (ref "CA4") (pin "-") (pinfunction "-_-") (pintype "passive"))
      (node (ref "DZA2") (pin "A") (pinfunction "A_A") (pintype "passive"))
      (node (ref "DZA4") (pin "A") (pinfunction "A_A") (pintype "passive"))
      (node (ref "I2C") (pin "1") (pinfunction "1_1") (pintype "passive"))
      (node (ref "J1") (pin "1") (pinfunction "1_1") (pintype "passive"))
      (node (ref "L12") (pin "K") (pinfunction "C_K") (pintype "passive"))
      (node (ref "L5") (pin "K") (pinfunction "C_K") (pintype "passive"))
      (node (ref "LI1") (pin "K") (pinfunction "C_K") (pintype "passive"))
      (node (ref "LI2") (pin "K") (pinfunction "C_K") (pintype "passive"))
      (node (ref "OK6") (pin "2") (pinfunction "C_2") (pintype "passive"))
      (node (ref "OK7") (pin "2") (pinfunction "C_2") (pintype "passive"))
      (node (ref "OLED_LCD") (pin "2") (pinfunction "2_2") (pintype "passive"))
      (node (ref "Q1") (pin "E") (pinfunction "E_E") (pintype "passive"))
      (node (ref "Q2") (pin "E") (pinfunction "E_E") (pintype "passive"))
      (node (ref "R1") (pin "2") (pinfunction "2_2") (pintype "passive"))
      (node (ref "R11") (pin "2") (pinfunction "2_2") (pintype "passive"))
      (node (ref "R13") (pin "2") (pinfunction "2_2") (pintype "passive"))
      (node (ref "R19") (pin "2") (pinfunction "2_2") (pintype "passive"))
      (node (ref "R2") (pin "2") (pinfunction "2_2") (pintype "passive"))
      (node (ref "R21") (pin "2") (pinfunction "2_2") (pintype "passive"))
      (node (ref "R22") (pin "2") (pinfunction "2_2") (pintype "passive"))
      (node (ref "R25") (pin "1") (pinfunction "1_1") (pintype "passive"))
      (node (ref "R26") (pin "1") (pinfunction "1_1") (pintype "passive"))
      (node (ref "R3") (pin "2") (pinfunction "2_2") (pintype "passive"))
      (node (ref "R4") (pin "2") (pinfunction "2_2") (pintype "passive"))
      (node (ref "R5") (pin "1") (pinfunction "1_1") (pintype "passive"))
      (node (ref "RA1") (pin "1") (pinfunction "1_1") (pintype "passive"))
      (node (ref "RA12") (pin "1") (pinfunction "1_1") (pintype "passive"))
      (node (ref "RA13") (pin "1") (pinfunction "1_1") (pintype "passive"))
      (node (ref "RA2") (pin "1") (pinfunction "1_1") (pintype "passive"))
      (node (ref "RA22") (pin "1") (pinfunction "1_1") (pintype "passive"))
      (node (ref "RA23") (pin "1") (pinfunction "1_1") (pintype "passive"))
      (node (ref "RLM35") (pin "1") (pinfunction "1_1") (pintype "passive"))
      (node (ref "SPI") (pin "1") (pinfunction "1_1") (pintype "passive"))
      (node (ref "U$1") (pin "IN-") (pinfunction "IN-_IN-") (pintype "passive"))
      (node (ref "U$1") (pin "OUT-") (pinfunction "OUT-_OUT-") (pintype "passive"))
      (node (ref "U1") (pin "2") (pinfunction "GND_2") (pintype "power_in"))
      (node (ref "U1") (pin "29") (pinfunction "GND_29") (pintype "power_in"))
    )
    (net (code "43") (name "Net-(D7-PadC)") (class "Default")
      (node (ref "D7") (pin "C") (pinfunction "C_C") (pintype "passive"))
      (node (ref "R12") (pin "1") (pinfunction "1_1") (pintype "passive"))
    )
    (net (code "44") (name "Net-(D8-PadC)") (class "Default")
      (node (ref "D8") (pin "C") (pinfunction "C_C") (pintype "passive"))
      (node (ref "R14") (pin "1") (pinfunction "1_1") (pintype "passive"))
    )
    (net (code "45") (name "Net-(L5-PadA)") (class "Default")
      (node (ref "L5") (pin "A") (pinfunction "A_A") (pintype "passive"))
      (node (ref "RL5") (pin "1") (pinfunction "1_1") (pintype "passive"))
    )
    (net (code "46") (name "Net-(L12-PadA)") (class "Default")
      (node (ref "L12") (pin "A") (pinfunction "A_A") (pintype "passive"))
      (node (ref "RL12") (pin "2") (pinfunction "2_2") (pintype "passive"))
    )
    (net (code "47") (name "Net-(LI1-PadA)") (class "Default")
      (node (ref "LI1") (pin "A") (pinfunction "A_A") (pintype "passive"))
      (node (ref "RLI1") (pin "2") (pinfunction "2_2") (pintype "passive"))
    )
    (net (code "48") (name "Net-(LI2-PadA)") (class "Default")
      (node (ref "LI2") (pin "A") (pinfunction "A_A") (pintype "passive"))
      (node (ref "RLI2") (pin "2") (pinfunction "2_2") (pintype "passive"))
    )
    (net (code "49") (name "Net-(LNO1-C)") (class "Default")
      (node (ref "D2") (pin "A") (pinfunction "A_A") (pintype "passive"))
      (node (ref "K1") (pin "A2") (pinfunction "A2_A2") (pintype "passive"))
      (node (ref "LNO1") (pin "K") (pinfunction "C_K") (pintype "passive"))
      (node (ref "Q1") (pin "C") (pinfunction "C_C") (pintype "passive"))
    )
    (net (code "50") (name "Net-(LNO1-PadA)") (class "Default")
      (node (ref "LNO1") (pin "A") (pinfunction "A_A") (pintype "passive"))
      (node (ref "R8") (pin "2") (pinfunction "2_2") (pintype "passive"))
    )
    (net (code "51") (name "Net-(LNO2-C)") (class "Default")
      (node (ref "D3") (pin "A") (pinfunction "A_A") (pintype "passive"))
      (node (ref "K3") (pin "A2") (pinfunction "A2_A2") (pintype "passive"))
      (node (ref "LNO2") (pin "K") (pinfunction "C_K") (pintype "passive"))
      (node (ref "Q2") (pin "C") (pinfunction "C_C") (pintype "passive"))
    )
    (net (code "52") (name "Net-(LNO2-PadA)") (class "Default")
      (node (ref "LNO2") (pin "A") (pinfunction "A_A") (pintype "passive"))
      (node (ref "R7") (pin "2") (pinfunction "2_2") (pintype "passive"))
    )
    (net (code "53") (name "Net-(LO1-C)") (class "Default")
      (node (ref "LO1") (pin "K") (pinfunction "C_K") (pintype "passive"))
      (node (ref "R21") (pin "1") (pinfunction "1_1") (pintype "passive"))
    )
    (net (code "54") (name "Net-(LO2-C)") (class "Default")
      (node (ref "LO2") (pin "K") (pinfunction "C_K") (pintype "passive"))
      (node (ref "R22") (pin "1") (pinfunction "1_1") (pintype "passive"))
    )
    (net (code "55") (name "Net-(OK1-C)") (class "Default")
      (node (ref "OK1") (pin "2") (pinfunction "C_2") (pintype "passive"))
      (node (ref "R2") (pin "1") (pinfunction "1_1") (pintype "passive"))
    )
    (net (code "56") (name "Net-(OK1-EMIT)") (class "Default")
      (node (ref "OK1") (pin "3") (pinfunction "EMIT_3") (pintype "passive"))
      (node (ref "Q1") (pin "B") (pinfunction "B_B") (pintype "passive"))
      (node (ref "R3") (pin "1") (pinfunction "1_1") (pintype "passive"))
    )
    (net (code "57") (name "Net-(OK2-C)") (class "Default")
      (node (ref "OK2") (pin "2") (pinfunction "C_2") (pintype "passive"))
      (node (ref "R4") (pin "1") (pinfunction "1_1") (pintype "passive"))
    )
    (net (code "58") (name "Net-(OK2-EMIT)") (class "Default")
      (node (ref "OK2") (pin "3") (pinfunction "EMIT_3") (pintype "passive"))
      (node (ref "Q2") (pin "B") (pinfunction "B_B") (pintype "passive"))
      (node (ref "R5") (pin "2") (pinfunction "2_2") (pintype "passive"))
    )
    (net (code "59") (name "Net-(OK3-A)") (class "Default")
      (node (ref "D1") (pin "C") (pinfunction "C_C") (pintype "passive"))
      (node (ref "OK3") (pin "1") (pinfunction "A_1") (pintype "passive"))
    )
    (net (code "60") (name "Net-(OK3-C)") (class "Default")
      (node (ref "OK3") (pin "2") (pinfunction "C_2") (pintype "passive"))
      (node (ref "R1") (pin "1") (pinfunction "1_1") (pintype "passive"))
    )
    (net (code "61") (name "Net-(OK3-COL)") (class "Default")
      (node (ref "D4") (pin "C") (pinfunction "C_C") (pintype "passive"))
      (node (ref "OK3") (pin "4") (pinfunction "COL_4") (pintype "passive"))
    )
    (net (code "62") (name "Net-(OK6-A)") (class "Default")
      (node (ref "C3") (pin "+") (pinfunction "+_+") (pintype "passive"))
      (node (ref "OK6") (pin "1") (pinfunction "A_1") (pintype "passive"))
      (node (ref "R11") (pin "1") (pinfunction "1_1") (pintype "passive"))
      (node (ref "R12") (pin "2") (pinfunction "2_2") (pintype "passive"))
      (node (ref "RLI1") (pin "1") (pinfunction "1_1") (pintype "passive"))
    )
    (net (code "63") (name "Net-(OK7-A)") (class "Default")
      (node (ref "C4") (pin "+") (pinfunction "+_+") (pintype "passive"))
      (node (ref "OK7") (pin "1") (pinfunction "A_1") (pintype "passive"))
      (node (ref "R13") (pin "1") (pinfunction "1_1") (pintype "passive"))
      (node (ref "R14") (pin "2") (pinfunction "2_2") (pintype "passive"))
      (node (ref "RLI2") (pin "1") (pinfunction "1_1") (pintype "passive"))
    )
    (net (code "64") (name "Net-(OK10-A)") (class "Default")
      (node (ref "D13") (pin "C") (pinfunction "C_C") (pintype "passive"))
      (node (ref "OK10") (pin "1") (pinfunction "A_1") (pintype "passive"))
    )
    (net (code "65") (name "Net-(OK10-C)") (class "Default")
      (node (ref "OK10") (pin "2") (pinfunction "C_2") (pintype "passive"))
      (node (ref "R19") (pin "1") (pinfunction "1_1") (pintype "passive"))
    )
    (net (code "66") (name "Net-(OK10-COL)") (class "Default")
      (node (ref "D14") (pin "C") (pinfunction "C_C") (pintype "passive"))
      (node (ref "OK10") (pin "4") (pinfunction "COL_4") (pintype "passive"))
    )
    (net (code "67") (name "Net-(RA2-Pad2)") (class "Default")
      (node (ref "RA2") (pin "2") (pinfunction "2_2") (pintype "passive"))
      (node (ref "RA3") (pin "1") (pinfunction "1_1") (pintype "passive"))
      (node (ref "S1") (pin "1") (pinfunction "COM_1") (pintype "passive"))
      (node (ref "S1") (pin "2") (pinfunction "COM_2") (pintype "passive"))
    )
    (net (code "68") (name "Net-(RA3-Pad2)") (class "Default")
      (node (ref "RA3") (pin "2") (pinfunction "2_2") (pintype "passive"))
      (node (ref "RA4") (pin "1") (pinfunction "1_1") (pintype "passive"))
      (node (ref "S2") (pin "1") (pinfunction "COM_1") (pintype "passive"))
      (node (ref "S2") (pin "2") (pinfunction "COM_2") (pintype "passive"))
    )
    (net (code "69") (name "Net-(RA4-Pad2)") (class "Default")
      (node (ref "RA4") (pin "2") (pinfunction "2_2") (pintype "passive"))
      (node (ref "RA5") (pin "1") (pinfunction "1_1") (pintype "passive"))
      (node (ref "S3") (pin "1") (pinfunction "COM_1") (pintype "passive"))
      (node (ref "S3") (pin "2") (pinfunction "COM_2") (pintype "passive"))
    )
    (net (code "70") (name "Net-(RA5-Pad2)") (class "Default")
      (node (ref "RA5") (pin "2") (pinfunction "2_2") (pintype "passive"))
      (node (ref "RA6") (pin "1") (pinfunction "1_1") (pintype "passive"))
      (node (ref "S4") (pin "1") (pinfunction "COM_1") (pintype "passive"))
      (node (ref "S4") (pin "2") (pinfunction "COM_2") (pintype "passive"))
    )
    (net (code "71") (name "Net-(U1-EN)") (class "Default")
      (node (ref "CA4") (pin "+") (pinfunction "+_+") (pintype "passive"))
      (node (ref "U1") (pin "16") (pinfunction "EN_16") (pintype "input"))
    )
    (net (code "72") (name "unconnected-(PAD1-P-Pad1)") (class "Default")
      (node (ref "PAD1") (pin "1") (pinfunction "P_1") (pintype "passive"))
    )
    (net (code "73") (name "unconnected-(PAD2-P-Pad1)") (class "Default")
      (node (ref "PAD2") (pin "1") (pinfunction "P_1") (pintype "passive"))
    )
    (net (code "74") (name "unconnected-(PAD3-P-Pad1)") (class "Default")
      (node (ref "PAD3") (pin "1") (pinfunction "P_1") (pintype "passive"))
    )
    (net (code "75") (name "unconnected-(PAD4-P-Pad1)") (class "Default")
      (node (ref "PAD4") (pin "1") (pinfunction "P_1") (pintype "passive"))
    )
    (net (code "76") (name "unconnected-(PAD5-P-Pad1)") (class "Default")
      (node (ref "PAD5") (pin "1") (pinfunction "P_1") (pintype "passive"))
    )
    (net (code "77") (name "unconnected-(PAD6-P-Pad1)") (class "Default")
      (node (ref "PAD6") (pin "1") (pinfunction "P_1") (pintype "passive"))
    )
    (net (code "78") (name "unconnected-(PAD7-P-Pad1)") (class "Default")
      (node (ref "PAD7") (pin "1") (pinfunction "P_1") (pintype "passive"))
    )
    (net (code "79") (name "unconnected-(PAD8-P-Pad1)") (class "Default")
      (node (ref "PAD8") (pin "1") (pinfunction "P_1") (pintype "passive"))
    )
    (net (code "80") (name "unconnected-(PAD9-P-Pad1)") (class "Default")
      (node (ref "PAD9") (pin "1") (pinfunction "P_1") (pintype "passive"))
    )
    (net (code "81") (name "unconnected-(PAD10-P-Pad1)") (class "Default")
      (node (ref "PAD10") (pin "1") (pinfunction "P_1") (pintype "passive"))
    )
    (net (code "82") (name "unconnected-(PAD11-P-Pad1)") (class "Default")
      (node (ref "PAD11") (pin "1") (pinfunction "P_1") (pintype "passive"))
    )
    (net (code "83") (name "unconnected-(PAD12-P-Pad1)") (class "Default")
      (node (ref "PAD12") (pin "1") (pinfunction "P_1") (pintype "passive"))
    )
    (net (code "84") (name "unconnected-(PAD13-P-Pad1)") (class "Default")
      (node (ref "PAD13") (pin "1") (pinfunction "P_1") (pintype "passive"))
    )
    (net (code "85") (name "unconnected-(PAD14-P-Pad1)") (class "Default")
      (node (ref "PAD14") (pin "1") (pinfunction "P_1") (pintype "passive"))
    )
    (net (code "86") (name "unconnected-(PAD15-P-Pad1)") (class "Default")
      (node (ref "PAD15") (pin "1") (pinfunction "P_1") (pintype "passive"))
    )
    (net (code "87") (name "unconnected-(PAD16-P-Pad1)") (class "Default")
      (node (ref "PAD16") (pin "1") (pinfunction "P_1") (pintype "passive"))
    )
    (net (code "88") (name "unconnected-(PAD17-P-Pad1)") (class "Default")
      (node (ref "PAD17") (pin "1") (pinfunction "P_1") (pintype "passive"))
    )
    (net (code "89") (name "unconnected-(PAD18-P-Pad1)") (class "Default")
      (node (ref "PAD18") (pin "1") (pinfunction "P_1") (pintype "passive"))
    )
    (net (code "90") (name "unconnected-(PAD19-P-Pad1)") (class "Default")
      (node (ref "PAD19") (pin "1") (pinfunction "P_1") (pintype "passive"))
    )
    (net (code "91") (name "unconnected-(PAD20-P-Pad1)") (class "Default")
      (node (ref "PAD20") (pin "1") (pinfunction "P_1") (pintype "passive"))
    )
    (net (code "92") (name "unconnected-(PAD21-P-Pad1)") (class "Default")
      (node (ref "PAD21") (pin "1") (pinfunction "P_1") (pintype "passive"))
    )
    (net (code "93") (name "unconnected-(PAD22-P-Pad1)") (class "Default")
      (node (ref "PAD22") (pin "1") (pinfunction "P_1") (pintype "passive"))
    )
    (net (code "94") (name "unconnected-(PAD23-P-Pad1)") (class "Default")
      (node (ref "PAD23") (pin "1") (pinfunction "P_1") (pintype "passive"))
    )
    (net (code "95") (name "unconnected-(PAD24-P-Pad1)") (class "Default")
      (node (ref "PAD24") (pin "1") (pinfunction "P_1") (pintype "passive"))
    )
    (net (code "96") (name "unconnected-(PAD25-P-Pad1)") (class "Default")
      (node (ref "PAD25") (pin "1") (pinfunction "P_1") (pintype "passive"))
    )
    (net (code "97") (name "unconnected-(PAD26-P-Pad1)") (class "Default")
      (node (ref "PAD26") (pin "1") (pinfunction "P_1") (pintype "passive"))
    )
    (net (code "98") (name "unconnected-(PAD27-P-Pad1)") (class "Default")
      (node (ref "PAD27") (pin "1") (pinfunction "P_1") (pintype "passive"))
    )
    (net (code "99") (name "unconnected-(PAD28-P-Pad1)") (class "Default")
      (node (ref "PAD28") (pin "1") (pinfunction "P_1") (pintype "passive"))
    )
    (net (code "100") (name "unconnected-(PAD29-P-Pad1)") (class "Default")
      (node (ref "PAD29") (pin "1") (pinfunction "P_1") (pintype "passive"))
    )
    (net (code "101") (name "unconnected-(PAD30-P-Pad1)") (class "Default")
      (node (ref "PAD30") (pin "1") (pinfunction "P_1") (pintype "passive"))
    )
    (net (code "102") (name "unconnected-(PAD31-P-Pad1)") (class "Default")
      (node (ref "PAD31") (pin "1") (pinfunction "P_1") (pintype "passive"))
    )
    (net (code "103") (name "unconnected-(PAD32-P-Pad1)") (class "Default")
      (node (ref "PAD32") (pin "1") (pinfunction "P_1") (pintype "passive"))
    )
    (net (code "104") (name "unconnected-(PAD33-P-Pad1)") (class "Default")
      (node (ref "PAD33") (pin "1") (pinfunction "P_1") (pintype "passive"))
    )
    (net (code "105") (name "unconnected-(PAD34-P-Pad1)") (class "Default")
      (node (ref "PAD34") (pin "1") (pinfunction "P_1") (pintype "passive"))
    )
    (net (code "106") (name "unconnected-(PAD35-P-Pad1)") (class "Default")
      (node (ref "PAD35") (pin "1") (pinfunction "P_1") (pintype "passive"))
    )
    (net (code "107") (name "unconnected-(PAD36-P-Pad1)") (class "Default")
      (node (ref "PAD36") (pin "1") (pinfunction "P_1") (pintype "passive"))
    )
    (net (code "108") (name "unconnected-(PAD37-P-Pad1)") (class "Default")
      (node (ref "PAD37") (pin "1") (pinfunction "P_1") (pintype "passive"))
    )
    (net (code "109") (name "unconnected-(PAD38-P-Pad1)") (class "Default")
      (node (ref "PAD38") (pin "1") (pinfunction "P_1") (pintype "passive"))
    )
    (net (code "110") (name "unconnected-(PAD39-P-Pad1)") (class "Default")
      (node (ref "PAD39") (pin "1") (pinfunction "P_1") (pintype "passive"))
    )
    (net (code "111") (name "unconnected-(PAD40-P-Pad1)") (class "Default")
      (node (ref "PAD40") (pin "1") (pinfunction "P_1") (pintype "passive"))
    )
    (net (code "112") (name "unconnected-(PAD41-P-Pad1)") (class "Default")
      (node (ref "PAD41") (pin "1") (pinfunction "P_1") (pintype "passive"))
    )
    (net (code "113") (name "unconnected-(PAD42-P-Pad1)") (class "Default")
      (node (ref "PAD42") (pin "1") (pinfunction "P_1") (pintype "passive"))
    )
    (net (code "114") (name "unconnected-(PAD43-P-Pad1)") (class "Default")
      (node (ref "PAD43") (pin "1") (pinfunction "P_1") (pintype "passive"))
    )
    (net (code "115") (name "unconnected-(PAD44-P-Pad1)") (class "Default")
      (node (ref "PAD44") (pin "1") (pinfunction "P_1") (pintype "passive"))
    )
    (net (code "116") (name "unconnected-(PAD45-P-Pad1)") (class "Default")
      (node (ref "PAD45") (pin "1") (pinfunction "P_1") (pintype "passive"))
    )
    (net (code "117") (name "unconnected-(PAD46-P-Pad1)") (class "Default")
      (node (ref "PAD46") (pin "1") (pinfunction "P_1") (pintype "passive"))
    )
    (net (code "118") (name "unconnected-(PAD47-P-Pad1)") (class "Default")
      (node (ref "PAD47") (pin "1") (pinfunction "P_1") (pintype "passive"))
    )
    (net (code "119") (name "unconnected-(PAD48-P-Pad1)") (class "Default")
      (node (ref "PAD48") (pin "1") (pinfunction "P_1") (pintype "passive"))
    )
    (net (code "120") (name "unconnected-(PAD49-P-Pad1)") (class "Default")
      (node (ref "PAD49") (pin "1") (pinfunction "P_1") (pintype "passive"))
    )
    (net (code "121") (name "unconnected-(PAD50-P-Pad1)") (class "Default")
      (node (ref "PAD50") (pin "1") (pinfunction "P_1") (pintype "passive"))
    )
    (net (code "122") (name "unconnected-(PAD51-P-Pad1)") (class "Default")
      (node (ref "PAD51") (pin "1") (pinfunction "P_1") (pintype "passive"))
    )
    (net (code "123") (name "unconnected-(PAD52-P-Pad1)") (class "Default")
      (node (ref "PAD52") (pin "1") (pinfunction "P_1") (pintype "passive"))
    )
    (net (code "124") (name "unconnected-(PAD53-P-Pad1)") (class "Default")
      (node (ref "PAD53") (pin "1") (pinfunction "P_1") (pintype "passive"))
    )
    (net (code "125") (name "unconnected-(PAD54-P-Pad1)") (class "Default")
      (node (ref "PAD54") (pin "1") (pinfunction "P_1") (pintype "passive"))
    )
    (net (code "126") (name "unconnected-(PAD55-P-Pad1)") (class "Default")
      (node (ref "PAD55") (pin "1") (pinfunction "P_1") (pintype "passive"))
    )
    (net (code "127") (name "unconnected-(PAD56-P-Pad1)") (class "Default")
      (node (ref "PAD56") (pin "1") (pinfunction "P_1") (pintype "passive"))
    )
    (net (code "128") (name "unconnected-(PAD57-P-Pad1)") (class "Default")
      (node (ref "PAD57") (pin "1") (pinfunction "P_1") (pintype "passive"))
    )
    (net (code "129") (name "unconnected-(PAD58-P-Pad1)") (class "Default")
      (node (ref "PAD58") (pin "1") (pinfunction "P_1") (pintype "passive"))
    )
    (net (code "130") (name "unconnected-(PAD59-P-Pad1)") (class "Default")
      (node (ref "PAD59") (pin "1") (pinfunction "P_1") (pintype "passive"))
    )
    (net (code "131") (name "unconnected-(PAD60-P-Pad1)") (class "Default")
      (node (ref "PAD60") (pin "1") (pinfunction "P_1") (pintype "passive"))
    )
    (net (code "132") (name "unconnected-(PAD61-P-Pad1)") (class "Default")
      (node (ref "PAD61") (pin "1") (pinfunction "P_1") (pintype "passive"))
    )
    (net (code "133") (name "unconnected-(PAD62-P-Pad1)") (class "Default")
      (node (ref "PAD62") (pin "1") (pinfunction "P_1") (pintype "passive"))
    )
    (net (code "134") (name "unconnected-(PAD63-P-Pad1)") (class "Default")
      (node (ref "PAD63") (pin "1") (pinfunction "P_1") (pintype "passive"))
    )
    (net (code "135") (name "unconnected-(PAD64-P-Pad1)") (class "Default")
      (node (ref "PAD64") (pin "1") (pinfunction "P_1") (pintype "passive"))
    )
    (net (code "136") (name "unconnected-(PAD65-P-Pad1)") (class "Default")
      (node (ref "PAD65") (pin "1") (pinfunction "P_1") (pintype "passive"))
    )
    (net (code "137") (name "unconnected-(PAD66-P-Pad1)") (class "Default")
      (node (ref "PAD66") (pin "1") (pinfunction "P_1") (pintype "passive"))
    )
    (net (code "138") (name "unconnected-(PAD67-P-Pad1)") (class "Default")
      (node (ref "PAD67") (pin "1") (pinfunction "P_1") (pintype "passive"))
    )
    (net (code "139") (name "unconnected-(PAD68-P-Pad1)") (class "Default")
      (node (ref "PAD68") (pin "1") (pinfunction "P_1") (pintype "passive"))
    )
    (net (code "140") (name "unconnected-(PAD69-P-Pad1)") (class "Default")
      (node (ref "PAD69") (pin "1") (pinfunction "P_1") (pintype "passive"))
    )
    (net (code "141") (name "unconnected-(PAD70-P-Pad1)") (class "Default")
      (node (ref "PAD70") (pin "1") (pinfunction "P_1") (pintype "passive"))
    )
    (net (code "142") (name "unconnected-(PAD71-P-Pad1)") (class "Default")
      (node (ref "PAD71") (pin "1") (pinfunction "P_1") (pintype "passive"))
    )
    (net (code "143") (name "unconnected-(PAD72-P-Pad1)") (class "Default")
      (node (ref "PAD72") (pin "1") (pinfunction "P_1") (pintype "passive"))
    )
    (net (code "144") (name "unconnected-(PAD73-P-Pad1)") (class "Default")
      (node (ref "PAD73") (pin "1") (pinfunction "P_1") (pintype "passive"))
    )
    (net (code "145") (name "unconnected-(PAD74-P-Pad1)") (class "Default")
      (node (ref "PAD74") (pin "1") (pinfunction "P_1") (pintype "passive"))
    )
    (net (code "146") (name "unconnected-(PAD75-P-Pad1)") (class "Default")
      (node (ref "PAD75") (pin "1") (pinfunction "P_1") (pintype "passive"))
    )
    (net (code "147") (name "unconnected-(PAD76-P-Pad1)") (class "Default")
      (node (ref "PAD76") (pin "1") (pinfunction "P_1") (pintype "passive"))
    )
    (net (code "148") (name "unconnected-(PAD77-P-Pad1)") (class "Default")
      (node (ref "PAD77") (pin "1") (pinfunction "P_1") (pintype "passive"))
    )
    (net (code "149") (name "unconnected-(PAD78-P-Pad1)") (class "Default")
      (node (ref "PAD78") (pin "1") (pinfunction "P_1") (pintype "passive"))
    )
    (net (code "150") (name "unconnected-(PAD79-P-Pad1)") (class "Default")
      (node (ref "PAD79") (pin "1") (pinfunction "P_1") (pintype "passive"))
    )
    (net (code "151") (name "unconnected-(PAD80-P-Pad1)") (class "Default")
      (node (ref "PAD80") (pin "1") (pinfunction "P_1") (pintype "passive"))
    )
    (net (code "152") (name "unconnected-(PAD81-P-Pad1)") (class "Default")
      (node (ref "PAD81") (pin "1") (pinfunction "P_1") (pintype "passive"))
    )
    (net (code "153") (name "unconnected-(PAD82-P-Pad1)") (class "Default")
      (node (ref "PAD82") (pin "1") (pinfunction "P_1") (pintype "passive"))
    )
    (net (code "154") (name "unconnected-(PAD83-P-Pad1)") (class "Default")
      (node (ref "PAD83") (pin "1") (pinfunction "P_1") (pintype "passive"))
    )
    (net (code "155") (name "unconnected-(PAD84-P-Pad1)") (class "Default")
      (node (ref "PAD84") (pin "1") (pinfunction "P_1") (pintype "passive"))
    )
    (net (code "156") (name "unconnected-(PAD85-P-Pad1)") (class "Default")
      (node (ref "PAD85") (pin "1") (pinfunction "P_1") (pintype "passive"))
    )
    (net (code "157") (name "unconnected-(PAD86-P-Pad1)") (class "Default")
      (node (ref "PAD86") (pin "1") (pinfunction "P_1") (pintype "passive"))
    )
    (net (code "158") (name "unconnected-(PAD87-P-Pad1)") (class "Default")
      (node (ref "PAD87") (pin "1") (pinfunction "P_1") (pintype "passive"))
    )
    (net (code "159") (name "unconnected-(PAD88-P-Pad1)") (class "Default")
      (node (ref "PAD88") (pin "1") (pinfunction "P_1") (pintype "passive"))
    )
    (net (code "160") (name "unconnected-(PAD89-P-Pad1)") (class "Default")
      (node (ref "PAD89") (pin "1") (pinfunction "P_1") (pintype "passive"))
    )
    (net (code "161") (name "unconnected-(PAD90-P-Pad1)") (class "Default")
      (node (ref "PAD90") (pin "1") (pinfunction "P_1") (pintype "passive"))
    )
    (net (code "162") (name "unconnected-(PAD91-P-Pad1)") (class "Default")
      (node (ref "PAD91") (pin "1") (pinfunction "P_1") (pintype "passive"))
    )
    (net (code "163") (name "unconnected-(PAD92-P-Pad1)") (class "Default")
      (node (ref "PAD92") (pin "1") (pinfunction "P_1") (pintype "passive"))
    )
    (net (code "164") (name "unconnected-(PAD93-P-Pad1)") (class "Default")
      (node (ref "PAD93") (pin "1") (pinfunction "P_1") (pintype "passive"))
    )
    (net (code "165") (name "unconnected-(PAD94-P-Pad1)") (class "Default")
      (node (ref "PAD94") (pin "1") (pinfunction "P_1") (pintype "passive"))
    )
    (net (code "166") (name "unconnected-(PAD95-P-Pad1)") (class "Default")
      (node (ref "PAD95") (pin "1") (pinfunction "P_1") (pintype "passive"))
    )
    (net (code "167") (name "unconnected-(PAD96-P-Pad1)") (class "Default")
      (node (ref "PAD96") (pin "1") (pinfunction "P_1") (pintype "passive"))
    )
    (net (code "168") (name "unconnected-(PAD97-P-Pad1)") (class "Default")
      (node (ref "PAD97") (pin "1") (pinfunction "P_1") (pintype "passive"))
    )
    (net (code "169") (name "unconnected-(PAD98-P-Pad1)") (class "Default")
      (node (ref "PAD98") (pin "1") (pinfunction "P_1") (pintype "passive"))
    )
    (net (code "170") (name "unconnected-(PAD99-P-Pad1)") (class "Default")
      (node (ref "PAD99") (pin "1") (pinfunction "P_1") (pintype "passive"))
    )
    (net (code "171") (name "unconnected-(PAD100-P-Pad1)") (class "Default")
      (node (ref "PAD100") (pin "1") (pinfunction "P_1") (pintype "passive"))
    )
    (net (code "172") (name "unconnected-(PAD101-P-Pad1)") (class "Default")
      (node (ref "PAD101") (pin "1") (pinfunction "P_1") (pintype "passive"))
    )
    (net (code "173") (name "unconnected-(PAD102-P-Pad1)") (class "Default")
      (node (ref "PAD102") (pin "1") (pinfunction "P_1") (pintype "passive"))
    )
    (net (code "174") (name "unconnected-(PAD103-P-Pad1)") (class "Default")
      (node (ref "PAD103") (pin "1") (pinfunction "P_1") (pintype "passive"))
    )
    (net (code "175") (name "unconnected-(PAD104-P-Pad1)") (class "Default")
      (node (ref "PAD104") (pin "1") (pinfunction "P_1") (pintype "passive"))
    )
  )
)
